# RTC_SEC.net
KiCad netlist of a schematic drawn in Altium Designer
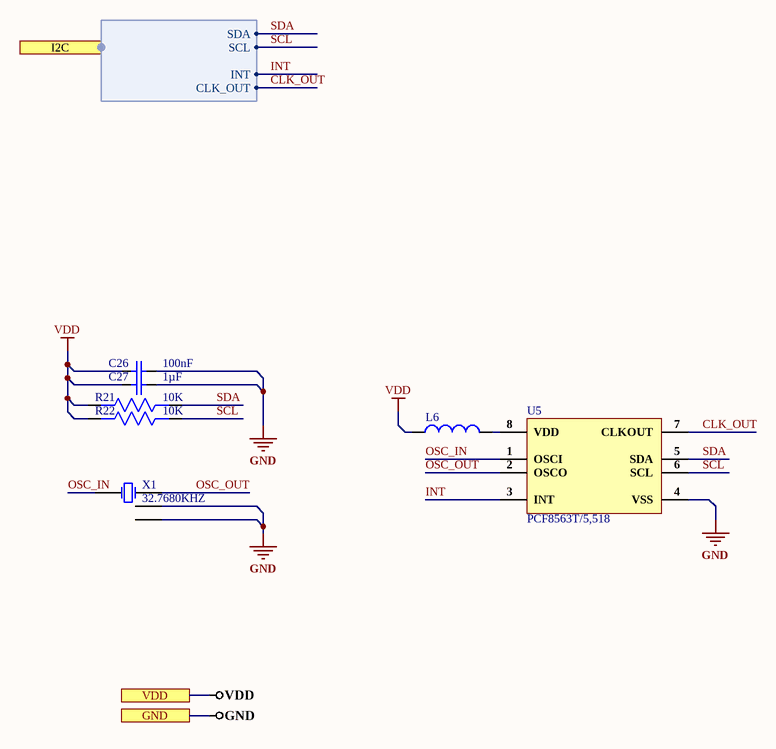
[diagram p0: RTC_SEC.SchDoc]

(export (version "E")
  (design (tool "Eeschema 10.0.6"))
  (components
    (comp (ref "C26")
      (value "100nF")
      (footprint "Cap0402")
      (description "Cap Ceramic 0.1uF 25V X7R 10% SMD 0402 125C Paper T/R")
      (fields
        (field (name "MANUFACTURER") "Yageo")
        (field (name "MANUFACTURER PART NUMBER") "CC0402KRX7R8BB104")
      )
      (libsource (lib "TT_IntLib") (part "CC0402KRX7R8BB104"))
    )
    (comp (ref "C27")
      (value "1µF")
      (footprint "Cap0402")
      (fields
        (field (name "MANUFACTURER") "Murata")
        (field (name "MANUFACTURER PART NUMBER") "GRM155R61E105KA12D")
        (field (name "TOLERANCE") "10%")
      )
      (libsource (lib "TT_IntLib") (part "GRM155R61E105KA12D"))
    )
    (comp (ref "L6")
      (value "MMZ0603S601CT000")
      (footprint "IND 0201")
      (description "FERRITE BEAD 600 OHM 0201 1LN")
      (fields (field (name "MANUFACTURER") "TDK") (field (name "TOLERANCE") "25%"))
      (libsource (lib "TT_IntLib") (part "MMZ0603S601CT000"))
    )
    (comp (ref "R21")
      (value "10K")
      (footprint "Res-0201")
      (description "GENERAL 0201 11% REEL (7INCH)")
      (fields
        (field (name "MANUFACTURER") "Yageo")
        (field (name "MANUFACTURER PART NUMBER") "RC0201FR-0710KL")
      )
      (libsource (lib "TT_IntLib") (part "RC0201FR-0710KL"))
    )
    (comp (ref "R22")
      (value "10K")
      (footprint "Res-0201")
      (description "GENERAL 0201 11% REEL (7INCH)")
      (fields
        (field (name "MANUFACTURER") "Yageo")
        (field (name "MANUFACTURER PART NUMBER") "RC0201FR-0710KL")
      )
      (libsource (lib "TT_IntLib") (part "RC0201FR-0710KL"))
    )
    (comp (ref "U5")
      (value "PCF8563T/5,518")
      (footprint "8-SO")
      (description "IC RTC CLK/CALENDAR I2C 8-SOIC")
      (libsource (lib "TT_IntLib") (part "PCF8563T/5,518"))
    )
    (comp (ref "X1")
      (value "32.7680KHZ")
      (footprint "CM200C32768DZFT")
      (description "CRYSTAL 32.7680KHZ 12.5PF SMD")
      (fields
        (field (name "MANUFACTURER") "Citizen")
        (field (name "MANUFACTURER PART NUMBER") "CM200C32768DZFT")
      )
      (libsource (lib "TT_IntLib") (part "CM200C32768DZFT"))
    )
  )
  (nets
    (net (code "2") (name "/CLK_OUT") (class "Default")
      (node (ref "U5") (pin "7") (pinfunction "CLKOUT_7") (pintype "passive"))
    )
    (net (code "3") (name "/INT") (class "Default")
      (node (ref "U5") (pin "3") (pinfunction "INT_3") (pintype "passive"))
    )
    (net (code "4") (name "/OSC_IN") (class "Default")
      (node (ref "U5") (pin "1") (pinfunction "OSCI_1") (pintype "passive"))
      (node (ref "X1") (pin "1") (pinfunction "OSC1_1") (pintype "passive"))
    )
    (net (code "5") (name "/OSC_OUT") (class "Default")
      (node (ref "U5") (pin "2") (pinfunction "OSCO_2") (pintype "passive"))
      (node (ref "X1") (pin "4") (pinfunction "OSC2_4") (pintype "passive"))
    )
    (net (code "6") (name "/SCL") (class "Default")
      (node (ref "R22") (pin "1") (pintype "passive"))
      (node (ref "U5") (pin "6") (pinfunction "SCL_6") (pintype "passive"))
    )
    (net (code "7") (name "/SDA") (class "Default")
      (node (ref "R21") (pin "1") (pintype "passive"))
      (node (ref "U5") (pin "5") (pinfunction "SDA_5") (pintype "passive"))
    )
    (net (code "9") (name "GND") (class "Default")
      (node (ref "C26") (pin "1") (pintype "passive"))
      (node (ref "C27") (pin "1") (pintype "passive"))
      (node (ref "U5") (pin "4") (pinfunction "VSS_4") (pintype "passive"))
      (node (ref "X1") (pin "2") (pinfunction "OSC3_2") (pintype "passive"))
      (node (ref "X1") (pin "3") (pinfunction "OSC4_3") (pintype "passive"))
    )
    (net (code "10") (name "Net-(U5-VDD)") (class "Default")
      (node (ref "L6") (pin "2") (pinfunction "2_2") (pintype "passive"))
      (node (ref "U5") (pin "8") (pinfunction "VDD_8") (pintype "passive"))
    )
    (net (code "11") (name "VDD") (class "Default")
      (node (ref "C26") (pin "2") (pintype "passive"))
      (node (ref "C27") (pin "2") (pintype "passive"))
      (node (ref "L6") (pin "1") (pinfunction "1_1") (pintype "passive"))
      (node (ref "R21") (pin "2") (pintype "passive"))
      (node (ref "R22") (pin "2") (pintype "passive"))
    )
  )
)
